# Ethe01Pro.net
KiCad netlist of a schematic drawn in Altium Designer
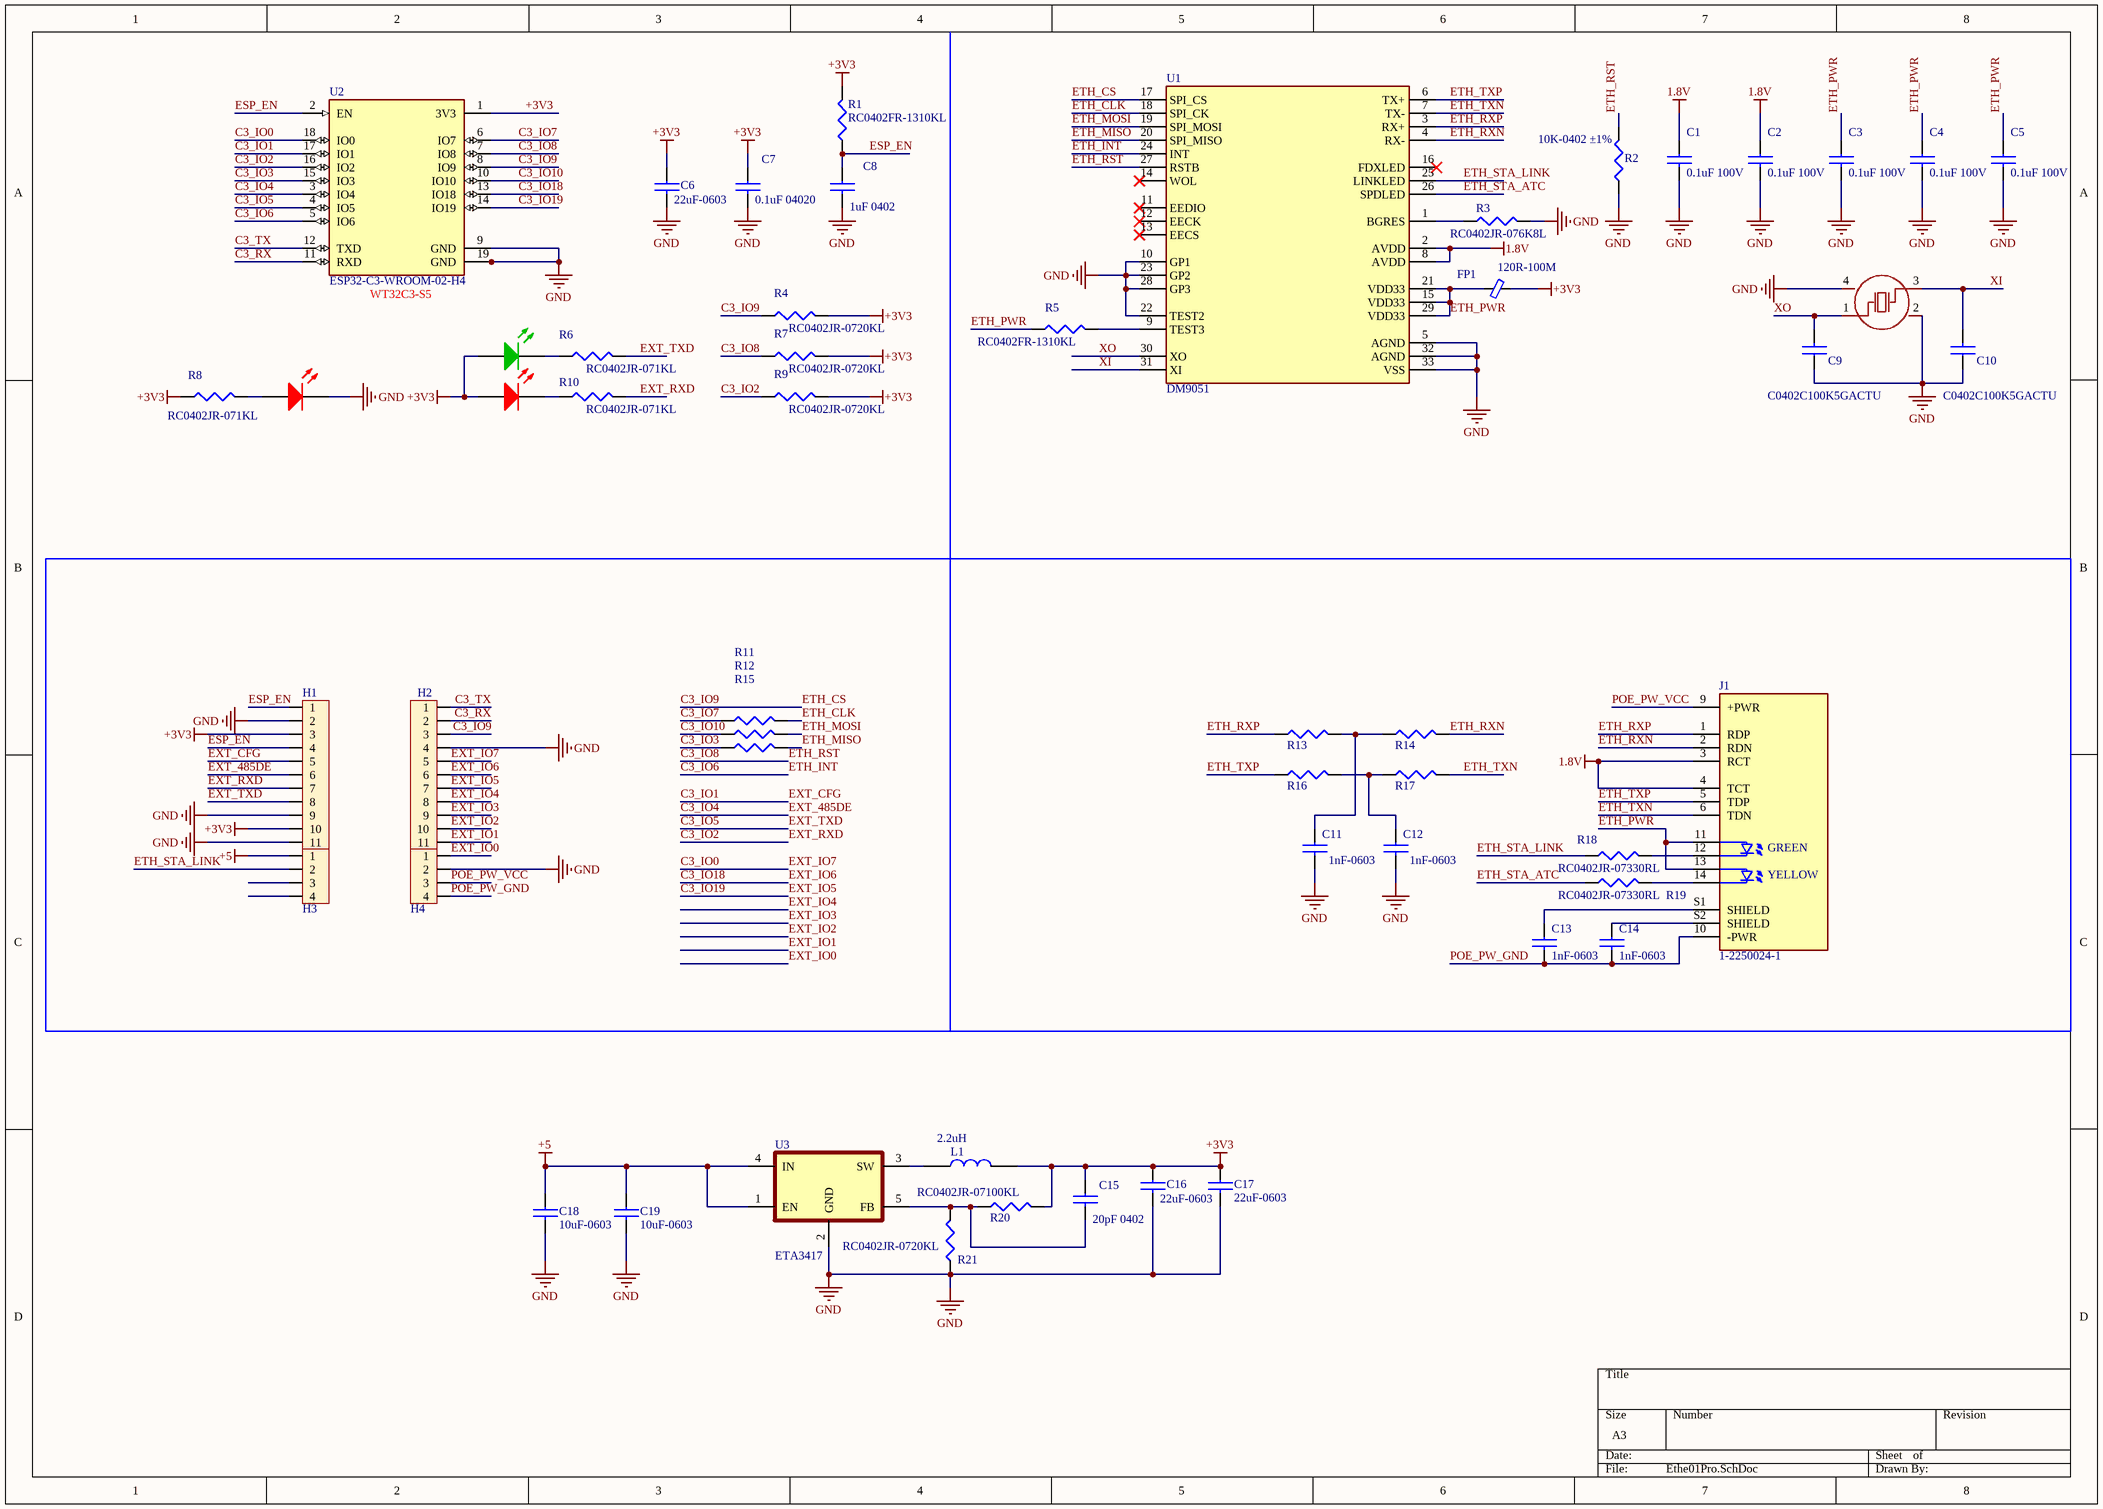
[diagram p0: Ethe01Pro.SchDoc]

(export (version "E")
  (design (tool "Eeschema 10.0.6"))
  (components
    (comp (ref "C1")
      (value "0.1uF 100V")
      (footprint "CAP0402")
      (description "Multilayer Ceramic Capacitor, 0.1 uF, 50 V, ï¿½ 10%, X7R, 0402 [1005 Metric]")
      (fields
        (field (name "MANUFACTURER") "Yageo")
        (field (name "MANUFACTURER PART NUMBER") "CC0402KRX7R8BB104")
      )
      (libsource (lib "Ethe01Pro") (part "CC0402KRX7R8BB104"))
    )
    (comp (ref "C2")
      (value "0.1uF 100V")
      (footprint "CAP0402")
      (description "Multilayer Ceramic Capacitor, 0.1 uF, 50 V, ï¿½ 10%, X7R, 0402 [1005 Metric]")
      (fields
        (field (name "MANUFACTURER") "Yageo")
        (field (name "MANUFACTURER PART NUMBER") "CC0402KRX7R8BB104")
      )
      (libsource (lib "Ethe01Pro") (part "CC0402KRX7R8BB104"))
    )
    (comp (ref "C3")
      (value "0.1uF 100V")
      (footprint "CAP0402")
      (description "Multilayer Ceramic Capacitor, 0.1 uF, 50 V, ï¿½ 10%, X7R, 0402 [1005 Metric]")
      (fields
        (field (name "MANUFACTURER") "Yageo")
        (field (name "MANUFACTURER PART NUMBER") "CC0402KRX7R8BB104")
      )
      (libsource (lib "Ethe01Pro") (part "CC0402KRX7R8BB104"))
    )
    (comp (ref "C4")
      (value "0.1uF 100V")
      (footprint "CAP0402")
      (description "Multilayer Ceramic Capacitor, 0.1 uF, 50 V, ï¿½ 10%, X7R, 0402 [1005 Metric]")
      (fields
        (field (name "MANUFACTURER") "Yageo")
        (field (name "MANUFACTURER PART NUMBER") "CC0402KRX7R8BB104")
      )
      (libsource (lib "Ethe01Pro") (part "CC0402KRX7R8BB104"))
    )
    (comp (ref "C5")
      (value "0.1uF 100V")
      (footprint "CAP0402")
      (description "Multilayer Ceramic Capacitor, 0.1 uF, 50 V, ï¿½ 10%, X7R, 0402 [1005 Metric]")
      (fields
        (field (name "MANUFACTURER") "Yageo")
        (field (name "MANUFACTURER PART NUMBER") "CC0402KRX7R8BB104")
      )
      (libsource (lib "Ethe01Pro") (part "CC0402KRX7R8BB104"))
    )
    (comp (ref "C6")
      (value "22uF-0603")
      (footprint "CAP0603")
      (description "CAP CER 22UF 10V X5R 0603")
      (fields (field (name "TOLERANCE") "±10%"))
      (libsource (lib "Ethe01Pro") (part "CC0603KRX5R6BB106"))
    )
    (comp (ref "C7")
      (value "0.1uF 04020")
      (footprint "CAP0402")
      (description "Multilayer Ceramic Capacitor, 0.1 uF, 50 V, ï¿½ 10%, X7R, 0402 [1005 Metric]")
      (fields
        (field (name "MANUFACTURER") "Yageo")
        (field (name "MANUFACTURER PART NUMBER") "CC0402KRX7R8BB104")
      )
      (libsource (lib "Ethe01Pro") (part "CC0402KRX7R8BB104"))
    )
    (comp (ref "C8")
      (value "1uF 0402")
      (footprint "CAP0402")
      (description "Multilayer Ceramic Capacitor, 1 uF, 100 V, ï¿½ 10%, X7R, 0402 [1005 Metric]")
      (fields
        (field (name "MANUFACTURER") "Yageo")
        (field (name "MANUFACTURER PART NUMBER") "CC0402KRX5R5BB105")
      )
      (libsource (lib "Ethe01Pro") (part "CC0402KRX5R5BB105"))
    )
    (comp (ref "C9")
      (value "C0402C100K5GACTU")
      (footprint "CAP0402")
      (description "Multilayer Ceramic Capacitor, 10 pF, 50 V, ï¿½ 10%, C0G (NP0), 0402 [1005 Metric]")
      (fields (field (name "MANUFACTURER") "KEMET") (field (name "TOLERANCE") "10%"))
      (libsource (lib "Ethe01Pro") (part "C0402C100K5GACTU"))
    )
    (comp (ref "C10")
      (value "C0402C100K5GACTU")
      (footprint "CAP0402")
      (description "Multilayer Ceramic Capacitor, 10 pF, 50 V, ï¿½ 10%, C0G (NP0), 0402 [1005 Metric]")
      (fields (field (name "MANUFACTURER") "KEMET") (field (name "TOLERANCE") "10%"))
      (libsource (lib "Ethe01Pro") (part "C0402C100K5GACTU"))
    )
    (comp (ref "C11")
      (value "1nF-0603")
      (footprint "CAP0603")
      (description "CAP CER 1000PF 50V X7R 0603")
      (fields
        (field (name "MANUFACTURER") "Yageo")
        (field (name "MANUFACTURER PART NUMBER") "CC0603KRX7R9BB102")
      )
      (libsource (lib "Ethe01Pro") (part "CC0603KRX7R9BB102"))
    )
    (comp (ref "C12")
      (value "1nF-0603")
      (footprint "CAP0603")
      (description "CAP CER 1000PF 50V X7R 0603")
      (fields
        (field (name "MANUFACTURER") "Yageo")
        (field (name "MANUFACTURER PART NUMBER") "CC0603KRX7R9BB102")
      )
      (libsource (lib "Ethe01Pro") (part "CC0603KRX7R9BB102"))
    )
    (comp (ref "C13")
      (value "1nF-0603")
      (footprint "CAP0603")
      (description "CAP CER 1000PF 50V X7R 0603")
      (fields
        (field (name "MANUFACTURER") "Yageo")
        (field (name "MANUFACTURER PART NUMBER") "CC0603KRX7R9BB102")
      )
      (libsource (lib "Ethe01Pro") (part "CC0603KRX7R9BB102"))
    )
    (comp (ref "C14")
      (value "1nF-0603")
      (footprint "CAP0603")
      (description "CAP CER 1000PF 50V X7R 0603")
      (fields
        (field (name "MANUFACTURER") "Yageo")
        (field (name "MANUFACTURER PART NUMBER") "CC0603KRX7R9BB102")
      )
      (libsource (lib "Ethe01Pro") (part "CC0603KRX7R9BB102"))
    )
    (comp (ref "C15")
      (value "20pF 0402")
      (footprint "CAP0402")
      (description "Multilayer Ceramic Capacitor, 10 pF, 50 V, ï¿½ 10%, C0G (NP0), 0402 [1005 Metric]")
      (fields
        (field (name "MANUFACTURER") "KEMET")
        (field (name "MANUFACTURER PART NUMBER") "C0402C100K5GACTU")
      )
      (libsource (lib "Ethe01Pro") (part "C0402C100K5GACTU"))
    )
    (comp (ref "C16")
      (value "22uF-0603")
      (footprint "CAP0603")
      (description "CAP CER 22UF 10V X5R 0603")
      (fields (field (name "TOLERANCE") "±10%"))
      (libsource (lib "Ethe01Pro") (part "CC0603KRX5R6BB106"))
    )
    (comp (ref "C17")
      (value "22uF-0603")
      (footprint "CAP0603")
      (description "CAP CER 22UF 10V X5R 0603")
      (fields (field (name "TOLERANCE") "±10%"))
      (libsource (lib "Ethe01Pro") (part "CC0603KRX5R6BB106"))
    )
    (comp (ref "C18")
      (value "10uF-0603")
      (footprint "CAP0603")
      (description "CAP CER 10UF 10V X5R 0603")
      (fields (field (name "TOLERANCE") "±10%"))
      (libsource (lib "Ethe01Pro") (part "CC0603KRX5R6BB106"))
    )
    (comp (ref "C19")
      (value "10uF-0603")
      (footprint "CAP0603")
      (description "CAP CER 10UF 10V X5R 0603")
      (fields (field (name "TOLERANCE") "±10%"))
      (libsource (lib "Ethe01Pro") (part "CC0603KRX5R6BB106"))
    )
    (comp (ref "FP1")
      (value "120R-100M")
      (footprint "FP0603")
      (description "MAF1608FAD121CT000")
      (libsource (lib "Huan") (part "FERRITE BREAD"))
    )
    (comp (ref "H1")
      (value "Header 11")
      (footprint "HDR1X11")
      (libsource (lib "Ethe01Pro") (part "Header 11"))
    )
    (comp (ref "H2") (value "Header 11") (footprint "HDR1X11") (libsource (lib "") (part "Header 11_1")))
    (comp (ref "H3") (value "Header 4") (footprint "HDR1X4") (libsource (lib "Ethe01Pro") (part "Header 4")))
    (comp (ref "H4") (value "Header 4") (footprint "HDR1X4") (libsource (lib "") (part "Header 4_1")))
    (comp (ref "J1")
      (value "1-2250024-1")
      (footprint "BEL_1-2250024-1")
      (description "1 Port RJ45 Magjack Connector Through Hole 10/100 Base-T, AutoMDIX, Power over Ethernet (PoE)")
      (fields (field (name "MF") "TRP Connector"))
      (libsource (lib "Ethe01Pro") (part "1-2250024-1"))
    )
    (comp (ref "L1")
      (value "2.2uH")
      (footprint "Cuon cam - 06030 - 7*7*3")
      (description "Wire-wound SMD Inductor 0630-2R2 2.2uH 7A")
      (fields (field (name "MF") "Abracon LLC") (field (name "MP") "ASPI-0425-1R0N-T3 (3K/REEL)"))
      (libsource (lib "Ethe01Pro") (part "Fixed Inductors"))
    )
    (comp (ref "LD1")
      (value "LED-GREEN")
      (footprint "LED_SMD0603_GREEN")
      (description "LED GREEN CLEAR 0603 SMD")
      (libsource (lib "Ethe01Pro") (part "LED_LTST-C191KGKT"))
    )
    (comp (ref "LD2")
      (value "LED-RED")
      (footprint "LED_SMD0603_RED")
      (description "LED RED CLEAR 0603 SMD")
      (fields
        (field (name "MANUFACTURER") "Lite-On Inc.")
        (field (name "MANUFACTURER PART NUMBER") "LTST-C191KRKT")
      )
      (libsource (lib "Ethe01Pro") (part "LED_LTST-C191KRKT"))
    )
    (comp (ref "LD3")
      (value "LED-RED")
      (footprint "LED_SMD0603_RED")
      (description "LED RED CLEAR 0603 SMD")
      (fields
        (field (name "MANUFACTURER") "Lite-On Inc.")
        (field (name "MANUFACTURER PART NUMBER") "LTST-C191KRKT")
      )
      (libsource (lib "Ethe01Pro") (part "LED_LTST-C191KRKT"))
    )
    (comp (ref "R1")
      (value "RC0402FR-1310KL")
      (footprint "RES0402")
      (description "SMD Chip Resistor, 10 kOhm, ï¿½ 1%, 63 mW, 0402 [1005 Metric], Thick Film, General Purpose")
      (fields (field (name "MANUFACTURER") "Yageo") (field (name "TOLERANCE") "1%"))
      (libsource (lib "Ethe01Pro") (part "RC0402FR-1310KL"))
    )
    (comp (ref "R2")
      (value "10K-0402 ±1%")
      (footprint "RES0402")
      (description "SMD Chip Resistor, 10 kOhm, ï¿½ 1%, 63 mW, 0402 [1005 Metric], Thick Film, General Purpose")
      (fields
        (field (name "MANUFACTURER") "Yageo")
        (field (name "MANUFACTURER PART NUMBER") "RC0402FR-1310KL")
      )
      (libsource (lib "Ethe01Pro") (part "RC0402FR-1310KL"))
    )
    (comp (ref "R3")
      (value "RC0402JR-076K8L")
      (footprint "RES0402")
      (description "Res Thick Film 0402 6.8K Ohm 5% 0.063W(1/16W) ±100ppm/C Pad SMD T/R")
      (fields (field (name "MANUFACTURER") "Yageo"))
      (libsource (lib "Ethe01Pro") (part "RC0402JR-076K8L"))
    )
    (comp (ref "R4")
      (value "RC0402JR-0720KL")
      (footprint "RES0402")
      (description "SMD Chip Resistor, 20 kOhm, ± 5%, 63 mW, 0402 [1005 Metric], Thick Film, General Purpose")
      (fields (field (name "MANUFACTURER") "Yageo"))
      (libsource (lib "Ethe01Pro") (part "RC0402JR-0720KL"))
    )
    (comp (ref "R5")
      (value "RC0402FR-1310KL")
      (footprint "RES0402")
      (description "SMD Chip Resistor, 10 kOhm, ï¿½ 1%, 63 mW, 0402 [1005 Metric], Thick Film, General Purpose")
      (fields (field (name "MANUFACTURER") "Yageo") (field (name "TOLERANCE") "1%"))
      (libsource (lib "Ethe01Pro") (part "RC0402FR-1310KL"))
    )
    (comp (ref "R6")
      (value "RC0402JR-071KL")
      (footprint "RES0402")
      (description "SMD Chip Resistor, 1 kOhm, ± 5%, 63 mW, 0402 [1005 Metric], Thick Film, General Purpose")
      (fields (field (name "MANUFACTURER") "Yageo") (field (name "TOLERANCE") "5%"))
      (libsource (lib "Ethe01Pro") (part "RC0402JR-071KL"))
    )
    (comp (ref "R7")
      (value "RC0402JR-0720KL")
      (footprint "RES0402")
      (description "SMD Chip Resistor, 20 kOhm, ± 5%, 63 mW, 0402 [1005 Metric], Thick Film, General Purpose")
      (fields (field (name "MANUFACTURER") "Yageo"))
      (libsource (lib "Ethe01Pro") (part "RC0402JR-0720KL"))
    )
    (comp (ref "R8")
      (value "RC0402JR-071KL")
      (footprint "RES0402")
      (description "SMD Chip Resistor, 1 kOhm, ± 5%, 63 mW, 0402 [1005 Metric], Thick Film, General Purpose")
      (fields (field (name "MANUFACTURER") "Yageo") (field (name "TOLERANCE") "5%"))
      (libsource (lib "Ethe01Pro") (part "RC0402JR-071KL"))
    )
    (comp (ref "R9")
      (value "RC0402JR-0720KL")
      (footprint "RES0402")
      (description "SMD Chip Resistor, 20 kOhm, ± 5%, 63 mW, 0402 [1005 Metric], Thick Film, General Purpose")
      (fields (field (name "MANUFACTURER") "Yageo"))
      (libsource (lib "Ethe01Pro") (part "RC0402JR-0720KL"))
    )
    (comp (ref "R10")
      (value "RC0402JR-071KL")
      (footprint "RES0402")
      (description "SMD Chip Resistor, 1 kOhm, ± 5%, 63 mW, 0402 [1005 Metric], Thick Film, General Purpose")
      (fields (field (name "MANUFACTURER") "Yageo") (field (name "TOLERANCE") "5%"))
      (libsource (lib "Ethe01Pro") (part "RC0402JR-071KL"))
    )
    (comp (ref "R11")
      (value "RC0402JR-0722RL")
      (footprint "RES0402")
      (description "SMD Chip Resistor, 22 Ohm, ï¿½ 5%, 63 mW, 0402 [1005 Metric], Thick Film, General Purpose")
      (fields (field (name "MANUFACTURER") "Yageo"))
      (libsource (lib "Ethe01Pro") (part "RC0402JR-0722RL"))
    )
    (comp (ref "R12")
      (value "RC0402JR-0722RL")
      (footprint "RES0402")
      (description "SMD Chip Resistor, 22 Ohm, ï¿½ 5%, 63 mW, 0402 [1005 Metric], Thick Film, General Purpose")
      (fields (field (name "MANUFACTURER") "Yageo"))
      (libsource (lib "Ethe01Pro") (part "RC0402JR-0722RL"))
    )
    (comp (ref "R13")
      (value "RC0402JR-0762RL")
      (footprint "RES0402")
      (description "Res Thick Film 0402 62 Ohm 5% 1/16W ±100ppm/°C Molded SMD SMD Paper T/R")
      (fields (field (name "MANUFACTURER") "Yageo"))
      (libsource (lib "Ethe01Pro") (part "RC0402JR-0762RL"))
    )
    (comp (ref "R14")
      (value "RC0402JR-0762RL")
      (footprint "RES0402")
      (description "Res Thick Film 0402 62 Ohm 5% 1/16W ±100ppm/°C Molded SMD SMD Paper T/R")
      (fields (field (name "MANUFACTURER") "Yageo"))
      (libsource (lib "Ethe01Pro") (part "RC0402JR-0762RL"))
    )
    (comp (ref "R15")
      (value "RC0402JR-0722RL")
      (footprint "RES0402")
      (description "SMD Chip Resistor, 22 Ohm, ï¿½ 5%, 63 mW, 0402 [1005 Metric], Thick Film, General Purpose")
      (fields (field (name "MANUFACTURER") "Yageo"))
      (libsource (lib "Ethe01Pro") (part "RC0402JR-0722RL"))
    )
    (comp (ref "R16")
      (value "RC0402JR-0762RL")
      (footprint "RES0402")
      (description "Res Thick Film 0402 62 Ohm 5% 1/16W ±100ppm/°C Molded SMD SMD Paper T/R")
      (fields (field (name "MANUFACTURER") "Yageo"))
      (libsource (lib "Ethe01Pro") (part "RC0402JR-0762RL"))
    )
    (comp (ref "R17")
      (value "RC0402JR-0762RL")
      (footprint "RES0402")
      (description "Res Thick Film 0402 62 Ohm 5% 1/16W ±100ppm/°C Molded SMD SMD Paper T/R")
      (fields (field (name "MANUFACTURER") "Yageo"))
      (libsource (lib "Ethe01Pro") (part "RC0402JR-0762RL"))
    )
    (comp (ref "R18")
      (value "RC0402JR-07330RL")
      (footprint "RES0402")
      (description "SMD Chip Resistor, 330 Ohm, ± 5%, 62.5 mW, 0402 [1005 Metric], Thick Film, General Purpose")
      (fields (field (name "MANUFACTURER") "Yageo"))
      (libsource (lib "Ethe01Pro") (part "RC0402JR-07330RL"))
    )
    (comp (ref "R19")
      (value "RC0402JR-07330RL")
      (footprint "RES0402")
      (description "SMD Chip Resistor, 330 Ohm, ± 5%, 62.5 mW, 0402 [1005 Metric], Thick Film, General Purpose")
      (fields (field (name "MANUFACTURER") "Yageo"))
      (libsource (lib "Ethe01Pro") (part "RC0402JR-07330RL"))
    )
    (comp (ref "R20")
      (value "RC0402JR-07100KL")
      (footprint "RES0402")
      (description "SMD Chip Resistor, 100 kOhm, ± 5%, 62.5 mW, 0402 [1005 Metric], Thick Film, General Purpose")
      (fields (field (name "MANUFACTURER") "Yageo") (field (name "TOLERANCE") "5%"))
      (libsource (lib "Ethe01Pro") (part "RC0402JR-07100KL"))
    )
    (comp (ref "R21")
      (value "RC0402JR-0720KL")
      (footprint "RES0402")
      (description "SMD Chip Resistor, 20 kOhm, ± 5%, 63 mW, 0402 [1005 Metric], Thick Film, General Purpose")
      (fields (field (name "MANUFACTURER") "Yageo"))
      (libsource (lib "Ethe01Pro") (part "RC0402JR-0720KL"))
    )
    (comp (ref "U1")
      (value "DM9051")
      (footprint "QFN50P500X500X100-33N")
      (description "SPI to Ethernet Controller - SQFN-32")
      (fields (field (name "MP") "LAN8740AI-EN-TR"))
      (libsource (lib "Ethe01Pro") (part "DM9051"))
    )
    (comp (ref "U2")
      (value "ESP32-C3-WROOM-02-H4")
      (footprint "MODULE_ESP32-C3-WROOM-02-H4")
      (fields (field (name "MF") "Espressif Systems"))
      (libsource (lib "Ethe01Pro") (part "ESP32-C3-WROOM-02-H4"))
    )
    (comp (ref "U3")
      (value "ETA3417")
      (footprint "SOT95P280X145-5N")
      (description "2.5A Continuous, 3A Peak, 3MHz Step-Down Converter in \r\nSOT23-5 Package")
      (fields (field (name "MP") "LP2985AIM5-2.8/NOPB"))
      (libsource (lib "Ethe01Pro") (part "ETA3417"))
    )
    (comp (ref "X1")
      (value "-")
      (footprint "OSC-SMD_4P-L3.2-W2.5-BL")
      (fields (field (name "MANUFACTURER") "TKD(泰晶)") (field (name "MANUFACTURER PART") "SX32Y025000BA1T"))
      (libsource (lib "Ethe01Pro") (part "SX32Y025000BA1T"))
    )
  )
  (nets
    (net (code "1") (name "+3V3") (class "Default")
      (node (ref "C15") (pin "1") (pinfunction "1_1") (pintype "passive"))
      (node (ref "C16") (pin "1") (pinfunction "1_1") (pintype "passive"))
      (node (ref "C17") (pin "1") (pinfunction "1_1") (pintype "passive"))
      (node (ref "C6") (pin "1") (pinfunction "1_1") (pintype "passive"))
      (node (ref "C7") (pin "1") (pinfunction "1_1") (pintype "passive"))
      (node (ref "FP1") (pin "2") (pintype "passive"))
      (node (ref "H1") (pin "10") (pinfunction "10_10") (pintype "passive"))
      (node (ref "H1") (pin "3") (pinfunction "3_3") (pintype "passive"))
      (node (ref "L1") (pin "2") (pinfunction "2_2") (pintype "passive"))
      (node (ref "LD1") (pin "1") (pinfunction "A_1") (pintype "passive"))
      (node (ref "LD3") (pin "1") (pinfunction "A_1") (pintype "passive"))
      (node (ref "R1") (pin "2") (pinfunction "2_2") (pintype "passive"))
      (node (ref "R20") (pin "2") (pinfunction "2_2") (pintype "passive"))
      (node (ref "R4") (pin "2") (pinfunction "2_2") (pintype "passive"))
      (node (ref "R7") (pin "2") (pinfunction "2_2") (pintype "passive"))
      (node (ref "R8") (pin "1") (pinfunction "1_1") (pintype "passive"))
      (node (ref "R9") (pin "2") (pinfunction "2_2") (pintype "passive"))
      (node (ref "U2") (pin "1") (pinfunction "3V3_1") (pintype "power_in"))
    )
    (net (code "2") (name "+5") (class "Default")
      (node (ref "C18") (pin "1") (pinfunction "1_1") (pintype "passive"))
      (node (ref "C19") (pin "1") (pinfunction "1_1") (pintype "passive"))
      (node (ref "H3") (pin "1") (pinfunction "1_1") (pintype "passive"))
      (node (ref "U3") (pin "1") (pinfunction "EN_1") (pintype "passive"))
      (node (ref "U3") (pin "4") (pinfunction "IN_4") (pintype "passive"))
    )
    (net (code "3") (name "/C3_IO0") (class "Default")
      (node (ref "H2") (pin "5") (pinfunction "5_5") (pintype "passive"))
      (node (ref "U2") (pin "18") (pinfunction "IO0_18") (pintype "bidirectional"))
    )
    (net (code "4") (name "/C3_IO1") (class "Default")
      (node (ref "H1") (pin "5") (pinfunction "5_5") (pintype "passive"))
      (node (ref "U2") (pin "17") (pinfunction "IO1_17") (pintype "bidirectional"))
    )
    (net (code "5") (name "/C3_IO2") (class "Default")
      (node (ref "H1") (pin "7") (pinfunction "7_7") (pintype "passive"))
      (node (ref "R10") (pin "2") (pinfunction "2_2") (pintype "passive"))
      (node (ref "R9") (pin "1") (pinfunction "1_1") (pintype "passive"))
      (node (ref "U2") (pin "16") (pinfunction "IO2_16") (pintype "bidirectional"))
    )
    (net (code "6") (name "/C3_IO3") (class "Default")
      (node (ref "R15") (pin "1") (pinfunction "1_1") (pintype "passive"))
      (node (ref "U2") (pin "15") (pinfunction "IO3_15") (pintype "bidirectional"))
    )
    (net (code "7") (name "/C3_IO4") (class "Default")
      (node (ref "H1") (pin "6") (pinfunction "6_6") (pintype "passive"))
      (node (ref "U2") (pin "3") (pinfunction "IO4_3") (pintype "bidirectional"))
    )
    (net (code "8") (name "/C3_IO5") (class "Default")
      (node (ref "H1") (pin "8") (pinfunction "8_8") (pintype "passive"))
      (node (ref "R6") (pin "2") (pinfunction "2_2") (pintype "passive"))
      (node (ref "U2") (pin "4") (pinfunction "IO5_4") (pintype "bidirectional"))
    )
    (net (code "9") (name "/C3_IO6") (class "Default")
      (node (ref "U1") (pin "24") (pinfunction "INT_24") (pintype "passive"))
      (node (ref "U2") (pin "5") (pinfunction "IO6_5") (pintype "bidirectional"))
    )
    (net (code "10") (name "/C3_IO7") (class "Default")
      (node (ref "R11") (pin "1") (pinfunction "1_1") (pintype "passive"))
      (node (ref "U2") (pin "6") (pinfunction "IO7_6") (pintype "bidirectional"))
    )
    (net (code "11") (name "/C3_IO8") (class "Default")
      (node (ref "R2") (pin "2") (pinfunction "2_2") (pintype "passive"))
      (node (ref "R7") (pin "1") (pinfunction "1_1") (pintype "passive"))
      (node (ref "U1") (pin "27") (pinfunction "RSTB_27") (pintype "passive"))
      (node (ref "U2") (pin "7") (pinfunction "IO8_7") (pintype "bidirectional"))
    )
    (net (code "12") (name "/C3_IO9") (class "Default")
      (node (ref "H2") (pin "3") (pinfunction "3_3") (pintype "passive"))
      (node (ref "R4") (pin "1") (pinfunction "1_1") (pintype "passive"))
      (node (ref "U1") (pin "17") (pinfunction "SPI_CS_17") (pintype "passive"))
      (node (ref "U2") (pin "8") (pinfunction "IO9_8") (pintype "bidirectional"))
    )
    (net (code "13") (name "/C3_IO10") (class "Default")
      (node (ref "R12") (pin "1") (pinfunction "1_1") (pintype "passive"))
      (node (ref "U2") (pin "10") (pinfunction "IO10_10") (pintype "bidirectional"))
    )
    (net (code "14") (name "/C3_IO18") (class "Default")
      (node (ref "H2") (pin "6") (pinfunction "6_6") (pintype "passive"))
      (node (ref "U2") (pin "13") (pinfunction "IO18_13") (pintype "bidirectional"))
    )
    (net (code "15") (name "/C3_IO19") (class "Default")
      (node (ref "H2") (pin "7") (pinfunction "7_7") (pintype "passive"))
      (node (ref "U2") (pin "14") (pinfunction "IO19_14") (pintype "bidirectional"))
    )
    (net (code "16") (name "/C3_RX") (class "Default")
      (node (ref "H2") (pin "2") (pinfunction "2_2") (pintype "passive"))
      (node (ref "U2") (pin "11") (pinfunction "RXD_11") (pintype "bidirectional"))
    )
    (net (code "17") (name "/C3_TX") (class "Default")
      (node (ref "H2") (pin "1") (pinfunction "1_1") (pintype "passive"))
      (node (ref "U2") (pin "12") (pinfunction "TXD_12") (pintype "bidirectional"))
    )
    (net (code "18") (name "/ESP_EN") (class "Default")
      (node (ref "C8") (pin "1") (pinfunction "1_1") (pintype "passive"))
      (node (ref "H1") (pin "1") (pinfunction "1_1") (pintype "passive"))
      (node (ref "H1") (pin "4") (pinfunction "4_4") (pintype "passive"))
      (node (ref "R1") (pin "1") (pinfunction "1_1") (pintype "passive"))
      (node (ref "U2") (pin "2") (pinfunction "EN_2") (pintype "input"))
    )
    (net (code "19") (name "/ETH_CLK") (class "Default")
      (node (ref "R11") (pin "2") (pinfunction "2_2") (pintype "passive"))
      (node (ref "U1") (pin "18") (pinfunction "SPI_CK_18") (pintype "passive"))
    )
    (net (code "20") (name "/ETH_MISO") (class "Default")
      (node (ref "R15") (pin "2") (pinfunction "2_2") (pintype "passive"))
      (node (ref "U1") (pin "20") (pinfunction "SPI_MISO_20") (pintype "passive"))
    )
    (net (code "21") (name "/ETH_MOSI") (class "Default")
      (node (ref "R12") (pin "2") (pinfunction "2_2") (pintype "passive"))
      (node (ref "U1") (pin "19") (pinfunction "SPI_MOSI_19") (pintype "passive"))
    )
    (net (code "22") (name "/ETH_PWR") (class "Default")
      (node (ref "C3") (pin "1") (pinfunction "1_1") (pintype "passive"))
      (node (ref "C4") (pin "1") (pinfunction "1_1") (pintype "passive"))
      (node (ref "C5") (pin "1") (pinfunction "1_1") (pintype "passive"))
      (node (ref "FP1") (pin "1") (pintype "passive"))
      (node (ref "J1") (pin "11") (pinfunction "11_11") (pintype "passive"))
      (node (ref "J1") (pin "13") (pinfunction "13_13") (pintype "passive"))
      (node (ref "R5") (pin "1") (pinfunction "1_1") (pintype "passive"))
      (node (ref "U1") (pin "15") (pinfunction "VDD33_15") (pintype "passive"))
      (node (ref "U1") (pin "21") (pinfunction "VDD33_21") (pintype "passive"))
      (node (ref "U1") (pin "29") (pinfunction "VDD33_29") (pintype "passive"))
    )
    (net (code "23") (name "/ETH_RXN") (class "Default")
      (node (ref "J1") (pin "2") (pinfunction "RDN_2") (pintype "passive"))
      (node (ref "R14") (pin "2") (pinfunction "2_2") (pintype "passive"))
      (node (ref "U1") (pin "4") (pinfunction "RX-_4") (pintype "passive"))
    )
    (net (code "24") (name "/ETH_RXP") (class "Default")
      (node (ref "J1") (pin "1") (pinfunction "RDP_1") (pintype "passive"))
      (node (ref "R13") (pin "1") (pinfunction "1_1") (pintype "passive"))
      (node (ref "U1") (pin "3") (pinfunction "RX+_3") (pintype "passive"))
    )
    (net (code "25") (name "/ETH_STA_ATC") (class "Default")
      (node (ref "R19") (pin "1") (pinfunction "1_1") (pintype "passive"))
      (node (ref "U1") (pin "26") (pinfunction "SPDLED_26") (pintype "passive"))
    )
    (net (code "26") (name "/ETH_STA_LINK") (class "Default")
      (node (ref "H3") (pin "2") (pinfunction "2_2") (pintype "passive"))
      (node (ref "R18") (pin "1") (pinfunction "1_1") (pintype "passive"))
      (node (ref "U1") (pin "25") (pinfunction "LINKLED_25") (pintype "passive"))
    )
    (net (code "27") (name "/ETH_TXN") (class "Default")
      (node (ref "J1") (pin "6") (pinfunction "TDN_6") (pintype "passive"))
      (node (ref "R17") (pin "2") (pinfunction "2_2") (pintype "passive"))
      (node (ref "U1") (pin "7") (pinfunction "TX-_7") (pintype "passive"))
    )
    (net (code "28") (name "/ETH_TXP") (class "Default")
      (node (ref "J1") (pin "5") (pinfunction "TDP_5") (pintype "passive"))
      (node (ref "R16") (pin "1") (pinfunction "1_1") (pintype "passive"))
      (node (ref "U1") (pin "6") (pinfunction "TX+_6") (pintype "passive"))
    )
    (net (code "29") (name "/EXT_IO0") (class "Default")
      (node (ref "H4") (pin "1") (pinfunction "1_1") (pintype "passive"))
    )
    (net (code "30") (name "/EXT_IO1") (class "Default")
      (node (ref "H2") (pin "11") (pinfunction "11_11") (pintype "passive"))
    )
    (net (code "31") (name "/EXT_IO2") (class "Default")
      (node (ref "H2") (pin "10") (pinfunction "10_10") (pintype "passive"))
    )
    (net (code "32") (name "/EXT_IO3") (class "Default")
      (node (ref "H2") (pin "9") (pinfunction "9_9") (pintype "passive"))
    )
    (net (code "33") (name "/EXT_IO4") (class "Default")
      (node (ref "H2") (pin "8") (pinfunction "8_8") (pintype "passive"))
    )
    (net (code "34") (name "/POE_PW_GND") (class "Default")
      (node (ref "C13") (pin "2") (pinfunction "2_2") (pintype "passive"))
      (node (ref "C14") (pin "2") (pinfunction "2_2") (pintype "passive"))
      (node (ref "H4") (pin "4") (pinfunction "4_4") (pintype "passive"))
      (node (ref "J1") (pin "10") (pinfunction "-PWR_10") (pintype "power_in"))
    )
    (net (code "35") (name "/POE_PW_VCC") (class "Default")
      (node (ref "H4") (pin "3") (pinfunction "3_3") (pintype "passive"))
      (node (ref "J1") (pin "9") (pinfunction "+PWR_9") (pintype "power_in"))
    )
    (net (code "36") (name "/XI") (class "Default")
      (node (ref "C10") (pin "2") (pinfunction "2_2") (pintype "passive"))
      (node (ref "U1") (pin "31") (pinfunction "XI_31") (pintype "passive"))
      (node (ref "X1") (pin "3") (pinfunction "OSC2_3") (pintype "passive"))
    )
    (net (code "37") (name "/XO") (class "Default")
      (node (ref "C9") (pin "2") (pinfunction "2_2") (pintype "passive"))
      (node (ref "U1") (pin "30") (pinfunction "XO_30") (pintype "passive"))
      (node (ref "X1") (pin "1") (pinfunction "OSC1_1") (pintype "passive"))
    )
    (net (code "38") (name "1.8V") (class "Default")
      (node (ref "C1") (pin "1") (pinfunction "1_1") (pintype "passive"))
      (node (ref "C2") (pin "1") (pinfunction "1_1") (pintype "passive"))
      (node (ref "J1") (pin "3") (pinfunction "RCT_3") (pintype "passive"))
      (node (ref "J1") (pin "4") (pinfunction "TCT_4") (pintype "passive"))
      (node (ref "U1") (pin "2") (pinfunction "AVDD_2") (pintype "passive"))
      (node (ref "U1") (pin "8") (pinfunction "AVDD_8") (pintype "passive"))
    )
    (net (code "39") (name "GND") (class "Default")
      (node (ref "C1") (pin "2") (pinfunction "2_2") (pintype "passive"))
      (node (ref "C10") (pin "1") (pinfunction "1_1") (pintype "passive"))
      (node (ref "C11") (pin "2") (pinfunction "2_2") (pintype "passive"))
      (node (ref "C12") (pin "2") (pinfunction "2_2") (pintype "passive"))
      (node (ref "C16") (pin "2") (pinfunction "2_2") (pintype "passive"))
      (node (ref "C17") (pin "2") (pinfunction "2_2") (pintype "passive"))
      (node (ref "C18") (pin "2") (pinfunction "2_2") (pintype "passive"))
      (node (ref "C19") (pin "2") (pinfunction "2_2") (pintype "passive"))
      (node (ref "C2") (pin "2") (pinfunction "2_2") (pintype "passive"))
      (node (ref "C3") (pin "2") (pinfunction "2_2") (pintype "passive"))
      (node (ref "C4") (pin "2") (pinfunction "2_2") (pintype "passive"))
      (node (ref "C5") (pin "2") (pinfunction "2_2") (pintype "passive"))
      (node (ref "C6") (pin "2") (pinfunction "2_2") (pintype "passive"))
      (node (ref "C7") (pin "2") (pinfunction "2_2") (pintype "passive"))
      (node (ref "C8") (pin "2") (pinfunction "2_2") (pintype "passive"))
      (node (ref "C9") (pin "1") (pinfunction "1_1") (pintype "passive"))
      (node (ref "H1") (pin "11") (pinfunction "11_11") (pintype "passive"))
      (node (ref "H1") (pin "2") (pinfunction "2_2") (pintype "passive"))
      (node (ref "H1") (pin "9") (pinfunction "9_9") (pintype "passive"))
      (node (ref "H2") (pin "4") (pinfunction "4_4") (pintype "passive"))
      (node (ref "H4") (pin "2") (pinfunction "2_2") (pintype "passive"))
      (node (ref "LD2") (pin "2") (pinfunction "K_2") (pintype "passive"))
      (node (ref "R2") (pin "1") (pinfunction "1_1") (pintype "passive"))
      (node (ref "R21") (pin "1") (pinfunction "1_1") (pintype "passive"))
      (node (ref "R3") (pin "2") (pinfunction "2_2") (pintype "passive"))
      (node (ref "U1") (pin "10") (pinfunction "GP1_10") (pintype "passive"))
      (node (ref "U1") (pin "22") (pinfunction "TEST2_22") (pintype "passive"))
      (node (ref "U1") (pin "23") (pinfunction "GP2_23") (pintype "passive"))
      (node (ref "U1") (pin "28") (pinfunction "GP3_28") (pintype "passive"))
      (node (ref "U1") (pin "32") (pinfunction "AGND_32") (pintype "passive"))
      (node (ref "U1") (pin "33") (pinfunction "VSS_33") (pintype "passive"))
      (node (ref "U1") (pin "5") (pinfunction "AGND_5") (pintype "passive"))
      (node (ref "U2") (pin "19") (pinfunction "GND_19") (pintype "power_in"))
      (node (ref "U2") (pin "20") (pinfunction "GND_20") (pintype "power_in"))
      (node (ref "U2") (pin "21") (pinfunction "GND_21") (pintype "power_in"))
      (node (ref "U2") (pin "22") (pinfunction "GND_22") (pintype "power_in"))
      (node (ref "U2") (pin "23") (pinfunction "GND_23") (pintype "power_in"))
      (node (ref "U2") (pin "24") (pinfunction "GND_24") (pintype "power_in"))
      (node (ref "U2") (pin "25") (pinfunction "GND_25") (pintype "power_in"))
      (node (ref "U2") (pin "26") (pinfunction "GND_26") (pintype "power_in"))
      (node (ref "U2") (pin "27") (pinfunction "GND_27") (pintype "power_in"))
      (node (ref "U2") (pin "28") (pinfunction "GND_28") (pintype "power_in"))
      (node (ref "U2") (pin "29") (pinfunction "GND_29") (pintype "power_in"))
      (node (ref "U2") (pin "30") (pinfunction "GND_30") (pintype "power_in"))
      (node (ref "U2") (pin "31") (pinfunction "GND_31") (pintype "power_in"))
      (node (ref "U2") (pin "32") (pinfunction "GND_32") (pintype "power_in"))
      (node (ref "U2") (pin "33") (pinfunction "GND_33") (pintype "power_in"))
      (node (ref "U2") (pin "34") (pinfunction "GND_34") (pintype "power_in"))
      (node (ref "U2") (pin "35") (pinfunction "GND_35") (pintype "power_in"))
      (node (ref "U2") (pin "36") (pinfunction "GND_36") (pintype "power_in"))
      (node (ref "U2") (pin "37") (pinfunction "GND_37") (pintype "power_in"))
      (node (ref "U2") (pin "38") (pinfunction "GND_38") (pintype "power_in"))
      (node (ref "U2") (pin "39") (pinfunction "GND_39") (pintype "power_in"))
      (node (ref "U2") (pin "9") (pinfunction "GND_9") (pintype "power_in"))
      (node (ref "U3") (pin "2") (pinfunction "GND_2") (pintype "power_in"))
      (node (ref "X1") (pin "2") (pinfunction "GND_2") (pintype "passive"))
      (node (ref "X1") (pin "4") (pinfunction "GND_4") (pintype "passive"))
    )
    (net (code "40") (name "Net-(C11-Pad1)") (class "Default")
      (node (ref "C11") (pin "1") (pinfunction "1_1") (pintype "passive"))
      (node (ref "R13") (pin "2") (pinfunction "2_2") (pintype "passive"))
      (node (ref "R14") (pin "1") (pinfunction "1_1") (pintype "passive"))
    )
    (net (code "41") (name "Net-(C12-Pad1)") (class "Default")
      (node (ref "C12") (pin "1") (pinfunction "1_1") (pintype "passive"))
      (node (ref "R16") (pin "2") (pinfunction "2_2") (pintype "passive"))
      (node (ref "R17") (pin "1") (pinfunction "1_1") (pintype "passive"))
    )
    (net (code "42") (name "Net-(C13-Pad1)") (class "Default")
      (node (ref "C13") (pin "1") (pinfunction "1_1") (pintype "passive"))
      (node (ref "J1") (pin "S1") (pinfunction "SHIELD_S1") (pintype "passive"))
    )
    (net (code "43") (name "Net-(C14-Pad1)") (class "Default")
      (node (ref "C14") (pin "1") (pinfunction "1_1") (pintype "passive"))
      (node (ref "J1") (pin "S2") (pinfunction "SHIELD_S2") (pintype "passive"))
    )
    (net (code "44") (name "Net-(J1-Pad12)") (class "Default")
      (node (ref "J1") (pin "12") (pinfunction "12_12") (pintype "passive"))
      (node (ref "R18") (pin "2") (pinfunction "2_2") (pintype "passive"))
    )
    (net (code "45") (name "Net-(J1-Pad14)") (class "Default")
      (node (ref "J1") (pin "14") (pinfunction "14_14") (pintype "passive"))
      (node (ref "R19") (pin "2") (pinfunction "2_2") (pintype "passive"))
    )
    (net (code "46") (name "Net-(LD1-K)") (class "Default")
      (node (ref "LD1") (pin "2") (pinfunction "K_2") (pintype "passive"))
      (node (ref "R6") (pin "1") (pinfunction "1_1") (pintype "passive"))
    )
    (net (code "47") (name "Net-(LD2-A)") (class "Default")
      (node (ref "LD2") (pin "1") (pinfunction "A_1") (pintype "passive"))
      (node (ref "R8") (pin "2") (pinfunction "2_2") (pintype "passive"))
    )
    (net (code "48") (name "Net-(LD3-K)") (class "Default")
      (node (ref "LD3") (pin "2") (pinfunction "K_2") (pintype "passive"))
      (node (ref "R10") (pin "1") (pinfunction "1_1") (pintype "passive"))
    )
    (net (code "49") (name "Net-(U1-BGRES)") (class "Default")
      (node (ref "R3") (pin "1") (pinfunction "1_1") (pintype "passive"))
      (node (ref "U1") (pin "1") (pinfunction "BGRES_1") (pintype "passive"))
    )
    (net (code "50") (name "Net-(U1-TEST3)") (class "Default")
      (node (ref "R5") (pin "2") (pinfunction "2_2") (pintype "passive"))
      (node (ref "U1") (pin "9") (pinfunction "TEST3_9") (pintype "passive"))
    )
    (net (code "51") (name "Net-(U3-FB)") (class "Default")
      (node (ref "C15") (pin "2") (pinfunction "2_2") (pintype "passive"))
      (node (ref "R20") (pin "1") (pinfunction "1_1") (pintype "passive"))
      (node (ref "R21") (pin "2") (pinfunction "2_2") (pintype "passive"))
      (node (ref "U3") (pin "5") (pinfunction "FB_5") (pintype "passive"))
    )
    (net (code "52") (name "Net-(U3-SW)") (class "Default")
      (node (ref "L1") (pin "1") (pinfunction "1_1") (pintype "passive"))
      (node (ref "U3") (pin "3") (pinfunction "SW_3") (pintype "passive"))
    )
    (net (code "53") (name "unconnected-(H3-Pad3)") (class "Default")
      (node (ref "H3") (pin "3") (pinfunction "3_3") (pintype "passive"))
    )
    (net (code "54") (name "unconnected-(H3-Pad4)") (class "Default")
      (node (ref "H3") (pin "4") (pinfunction "4_4") (pintype "passive"))
    )
    (net (code "55") (name "unconnected-(U1-EECK-Pad12)") (class "Default")
      (node (ref "U1") (pin "12") (pinfunction "EECK_12") (pintype "passive+no_connect"))
    )
    (net (code "56") (name "unconnected-(U1-EECS-Pad13)") (class "Default")
      (node (ref "U1") (pin "13") (pinfunction "EECS_13") (pintype "passive+no_connect"))
    )
    (net (code "57") (name "unconnected-(U1-EEDIO-Pad11)") (class "Default")
      (node (ref "U1") (pin "11") (pinfunction "EEDIO_11") (pintype "passive+no_connect"))
    )
    (net (code "58") (name "unconnected-(U1-FDXLED-Pad16)") (class "Default")
      (node (ref "U1") (pin "16") (pinfunction "FDXLED_16") (pintype "passive+no_connect"))
    )
    (net (code "59") (name "unconnected-(U1-WOL-Pad14)") (class "Default")
      (node (ref "U1") (pin "14") (pinfunction "WOL_14") (pintype "passive+no_connect"))
    )
  )
)
